# Juniordesignfilterandenvelopecircuitsche.net
KiCad netlist of a schematic drawn in EAGLE
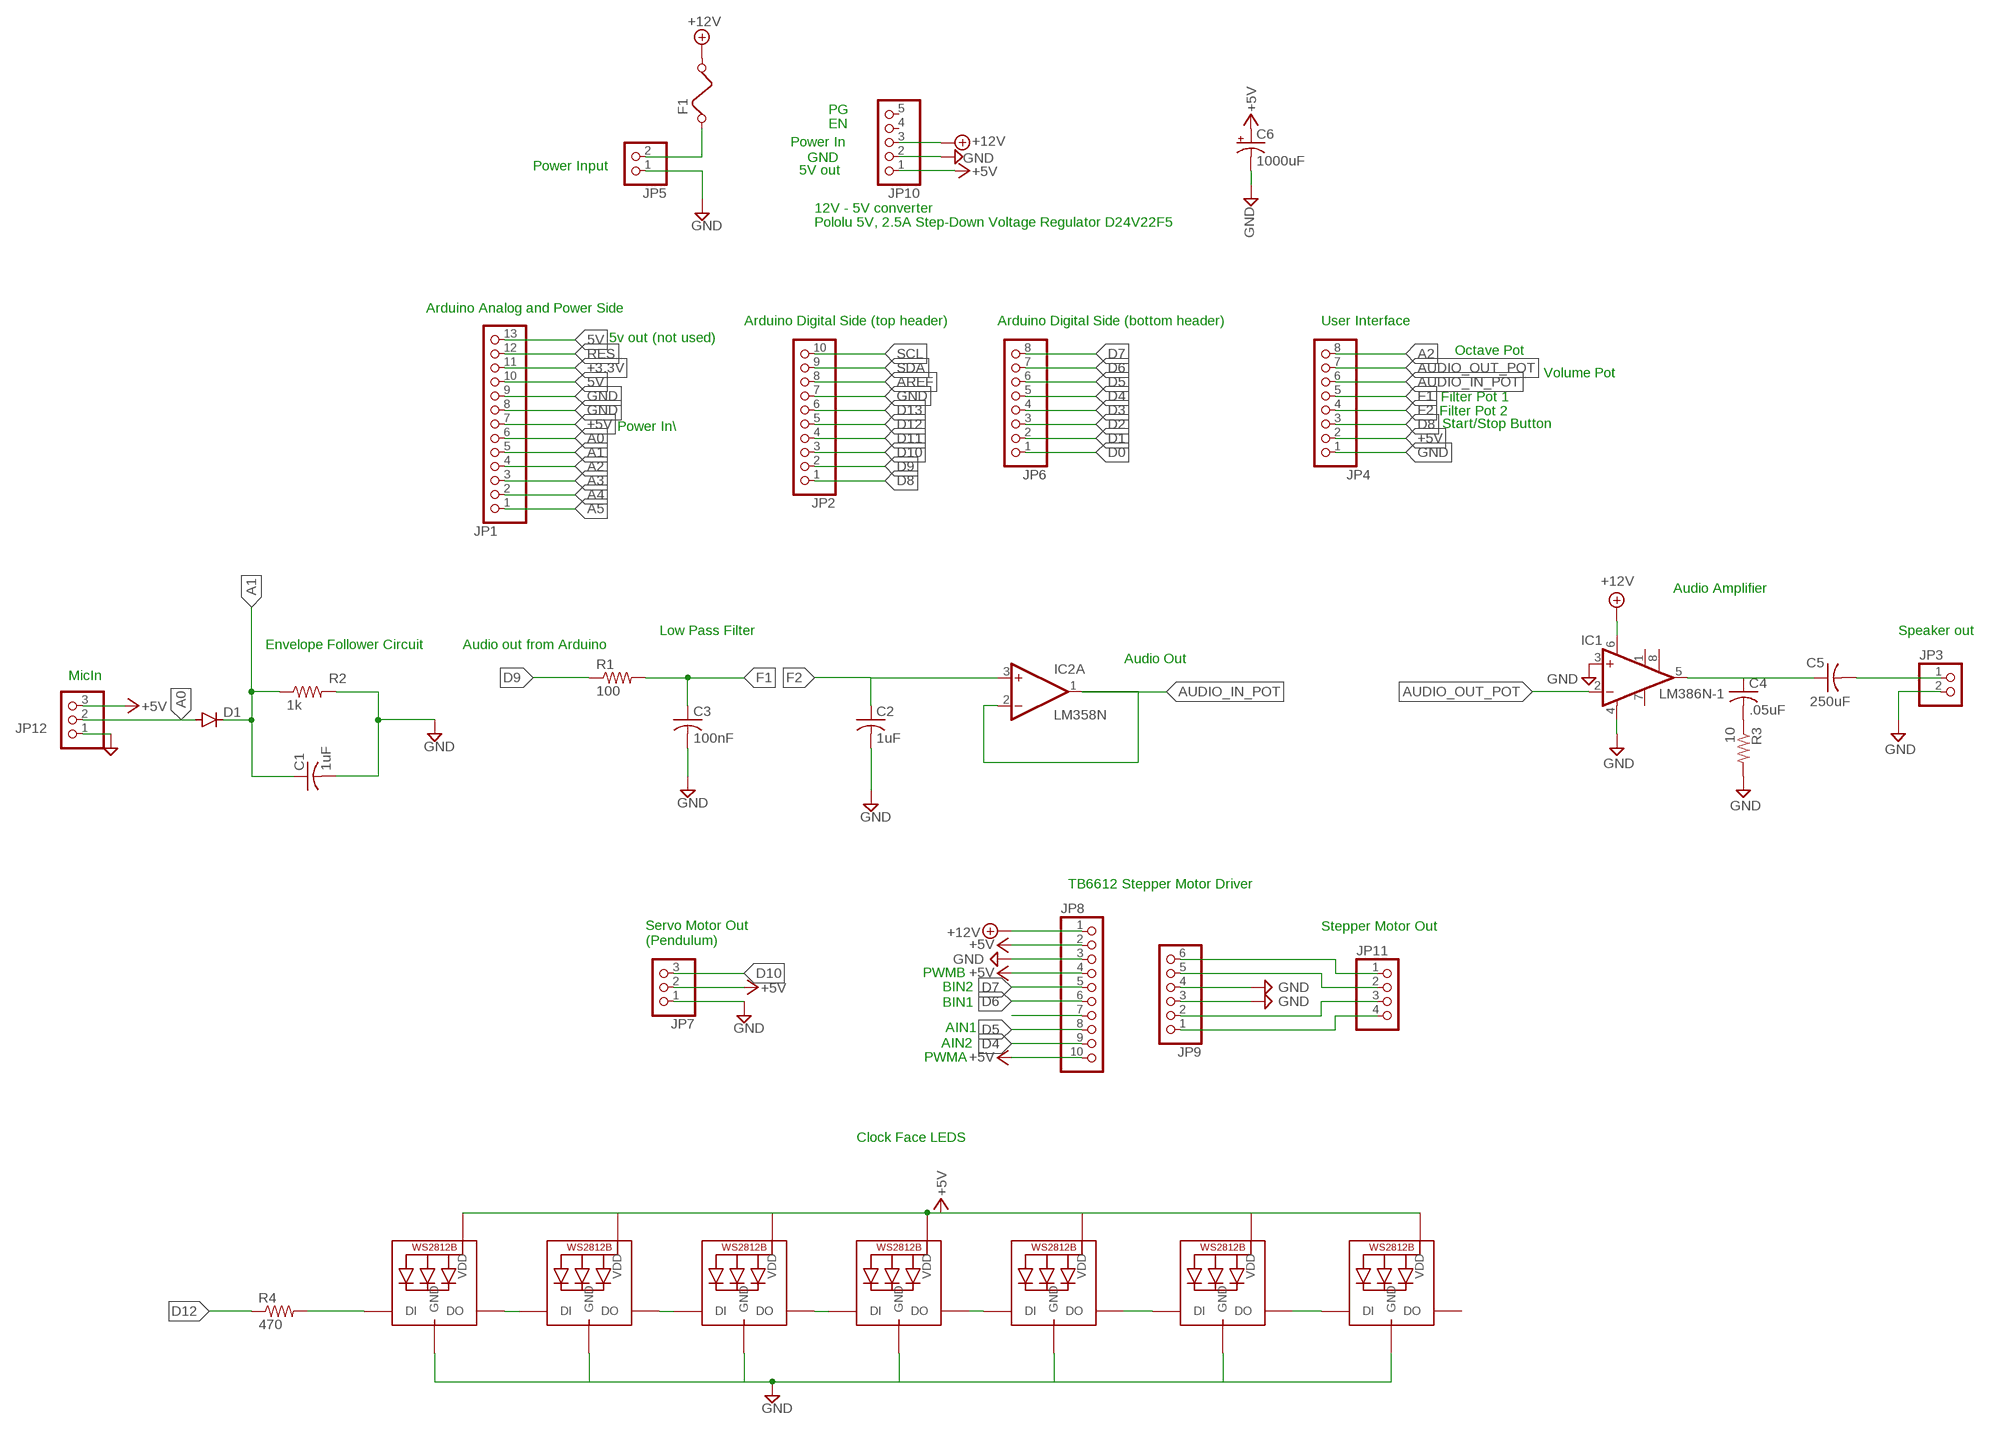
[diagram p0: schematic, sheet 1]

(export (version "E")
  (design (tool "Eeschema 10.0.6"))
  (components
    (comp (ref "C1")
      (value "1uF")
      (footprint "eagle-import:C025-050X050")
      (libsource (lib "eagle-import") (part "C-US025-050X050"))
    )
    (comp (ref "C2")
      (value "1uF")
      (footprint "eagle-import:C025-040X050")
      (libsource (lib "eagle-import") (part "C-US025-040X050"))
    )
    (comp (ref "C3")
      (value "100nF")
      (footprint "eagle-import:C025-040X050")
      (libsource (lib "eagle-import") (part "C-US025-040X050"))
    )
    (comp (ref "C4")
      (value ".05uF")
      (footprint "eagle-import:C025-040X050")
      (libsource (lib "eagle-import") (part "C-US025-040X050"))
    )
    (comp (ref "C5")
      (value "250uF")
      (footprint "eagle-import:C025-040X050")
      (libsource (lib "eagle-import") (part "C-US025-040X050"))
    )
    (comp (ref "C6")
      (value "1000uF")
      (footprint "eagle-import:E5-8,5")
      (libsource (lib "eagle-import") (part "CPOL-USE5-8.5"))
    )
    (comp (ref "D1")
      (value "1N4148DO35-7")
      (footprint "eagle-import:DO35-7")
      (libsource (lib "eagle-import") (part "1N4148DO35-7"))
    )
    (comp (ref "F1")
      (value "FUSE")
      (footprint "eagle-import:FUSE")
      (libsource (lib "eagle-import") (part "FUSE"))
    )
    (comp (ref "IC1")
      (value "LM386N-1")
      (footprint "eagle-import:DIL08")
      (libsource (lib "eagle-import") (part "LM386?-N1"))
    )
    (comp (ref "IC2")
      (value "LM358N")
      (footprint "eagle-import:DIL08")
      (libsource (lib "eagle-import") (part "LM358N"))
    )
    (comp (ref "JP1")
      (value "PINHD-1X13")
      (footprint "eagle-import:1X13")
      (libsource (lib "eagle-import") (part "PINHD-1X13"))
    )
    (comp (ref "JP2")
      (value "PINHD-1X10")
      (footprint "eagle-import:1X10")
      (libsource (lib "eagle-import") (part "PINHD-1X10"))
    )
    (comp (ref "JP3")
      (value "PINHD-1X2")
      (footprint "eagle-import:1X02")
      (libsource (lib "eagle-import") (part "PINHD-1X2"))
    )
    (comp (ref "JP4")
      (value "PINHD-1X8")
      (footprint "eagle-import:1X08")
      (libsource (lib "eagle-import") (part "PINHD-1X8"))
    )
    (comp (ref "JP5")
      (value "PINHD-1X2")
      (footprint "eagle-import:1X02")
      (libsource (lib "eagle-import") (part "PINHD-1X2"))
    )
    (comp (ref "JP6")
      (value "PINHD-1X8")
      (footprint "eagle-import:1X08")
      (libsource (lib "eagle-import") (part "PINHD-1X8"))
    )
    (comp (ref "JP7")
      (value "PINHD-1X3")
      (footprint "eagle-import:1X03")
      (libsource (lib "eagle-import") (part "PINHD-1X3"))
    )
    (comp (ref "JP8")
      (value "PINHD-1X10")
      (footprint "eagle-import:1X10")
      (libsource (lib "eagle-import") (part "PINHD-1X10"))
    )
    (comp (ref "JP9")
      (value "PINHD-1X6")
      (footprint "eagle-import:1X06")
      (libsource (lib "eagle-import") (part "PINHD-1X6"))
    )
    (comp (ref "JP10")
      (value "PINHD-1X5")
      (footprint "eagle-import:1X05")
      (libsource (lib "eagle-import") (part "PINHD-1X5"))
    )
    (comp (ref "JP11")
      (value "PINHD-1X4")
      (footprint "eagle-import:1X04")
      (libsource (lib "eagle-import") (part "PINHD-1X4"))
    )
    (comp (ref "JP12")
      (value "PINHD-1X3")
      (footprint "eagle-import:1X03")
      (libsource (lib "eagle-import") (part "PINHD-1X3"))
    )
    (comp (ref "LED2")
      (value "WS2812B_5050N")
      (footprint "eagle-import:WS2812B-NARROW")
      (libsource (lib "eagle-import") (part "WS2812B_5050N"))
    )
    (comp (ref "LED3")
      (value "WS2812B_5050N")
      (footprint "eagle-import:WS2812B-NARROW")
      (libsource (lib "eagle-import") (part "WS2812B_5050N"))
    )
    (comp (ref "LED4")
      (value "WS2812B_5050N")
      (footprint "eagle-import:WS2812B-NARROW")
      (libsource (lib "eagle-import") (part "WS2812B_5050N"))
    )
    (comp (ref "LED5")
      (value "WS2812B_5050N")
      (footprint "eagle-import:WS2812B-NARROW")
      (libsource (lib "eagle-import") (part "WS2812B_5050N"))
    )
    (comp (ref "LED6")
      (value "WS2812B_5050N")
      (footprint "eagle-import:WS2812B-NARROW")
      (libsource (lib "eagle-import") (part "WS2812B_5050N"))
    )
    (comp (ref "LED7")
      (value "WS2812B_5050N")
      (footprint "eagle-import:WS2812B-NARROW")
      (libsource (lib "eagle-import") (part "WS2812B_5050N"))
    )
    (comp (ref "LED8")
      (value "WS2812B_5050N")
      (footprint "eagle-import:WS2812B-NARROW")
      (libsource (lib "eagle-import") (part "WS2812B_5050N"))
    )
    (comp (ref "R1")
      (value "100")
      (footprint "eagle-import:0204_7")
      (libsource (lib "eagle-import") (part "R-US_0204/7"))
    )
    (comp (ref "R2")
      (value "1k")
      (footprint "eagle-import:0204_7")
      (libsource (lib "eagle-import") (part "R-US_0204/7"))
    )
    (comp (ref "R3")
      (value "10")
      (footprint "eagle-import:0204_7")
      (libsource (lib "eagle-import") (part "R-US_0204/7"))
    )
    (comp (ref "R4")
      (value "470")
      (footprint "eagle-import:0204_7")
      (libsource (lib "eagle-import") (part "R-US_0204/7"))
    )
  )
  (nets
    (net (code "1") (name "+3.3V") (class "Default")
      (node (ref "JP1") (pin "11") (pinfunction "11_11") (pintype "passive"))
    )
    (net (code "2") (name "+5V") (class "Default")
      (node (ref "C6") (pin "+") (pinfunction "+_+") (pintype "passive"))
      (node (ref "JP1") (pin "7") (pinfunction "7_7") (pintype "passive"))
      (node (ref "JP10") (pin "1") (pinfunction "1_1") (pintype "passive"))
      (node (ref "JP12") (pin "3") (pinfunction "3_3") (pintype "passive"))
      (node (ref "JP4") (pin "2") (pinfunction "2_2") (pintype "passive"))
      (node (ref "JP7") (pin "2") (pinfunction "2_2") (pintype "passive"))
      (node (ref "JP8") (pin "10") (pinfunction "10_10") (pintype "passive"))
      (node (ref "JP8") (pin "2") (pinfunction "2_2") (pintype "passive"))
      (node (ref "JP8") (pin "4") (pinfunction "4_4") (pintype "passive"))
      (node (ref "LED2") (pin "1-VDD") (pinfunction "VDD_1-VDD") (pintype "power_in"))
      (node (ref "LED3") (pin "1-VDD") (pinfunction "VDD_1-VDD") (pintype "power_in"))
      (node (ref "LED4") (pin "1-VDD") (pinfunction "VDD_1-VDD") (pintype "power_in"))
      (node (ref "LED5") (pin "1-VDD") (pinfunction "VDD_1-VDD") (pintype "power_in"))
      (node (ref "LED6") (pin "1-VDD") (pinfunction "VDD_1-VDD") (pintype "power_in"))
      (node (ref "LED7") (pin "1-VDD") (pinfunction "VDD_1-VDD") (pintype "power_in"))
      (node (ref "LED8") (pin "1-VDD") (pinfunction "VDD_1-VDD") (pintype "power_in"))
    )
    (net (code "3") (name "+12V") (class "Default")
      (node (ref "F1") (pin "2") (pinfunction "2_2") (pintype "passive"))
      (node (ref "IC1") (pin "6") (pinfunction "VS_6") (pintype "power_in"))
      (node (ref "JP10") (pin "3") (pinfunction "3_3") (pintype "passive"))
      (node (ref "JP8") (pin "1") (pinfunction "1_1") (pintype "passive"))
    )
    (net (code "4") (name "5V") (class "Default")
      (node (ref "JP1") (pin "10") (pinfunction "10_10") (pintype "passive"))
      (node (ref "JP1") (pin "13") (pinfunction "13_13") (pintype "passive"))
    )
    (net (code "5") (name "A0") (class "Default")
      (node (ref "D1") (pin "A") (pinfunction "A_A") (pintype "passive"))
      (node (ref "JP1") (pin "6") (pinfunction "6_6") (pintype "passive"))
      (node (ref "JP12") (pin "2") (pinfunction "2_2") (pintype "passive"))
    )
    (net (code "6") (name "A1") (class "Default")
      (node (ref "C1") (pin "1") (pinfunction "1_1") (pintype "passive"))
      (node (ref "D1") (pin "C") (pinfunction "C_C") (pintype "passive"))
      (node (ref "JP1") (pin "5") (pinfunction "5_5") (pintype "passive"))
      (node (ref "R2") (pin "1") (pinfunction "1_1") (pintype "passive"))
    )
    (net (code "7") (name "A2") (class "Default")
      (node (ref "JP1") (pin "4") (pinfunction "4_4") (pintype "passive"))
      (node (ref "JP4") (pin "8") (pinfunction "8_8") (pintype "passive"))
    )
    (net (code "8") (name "A3") (class "Default")
      (node (ref "JP1") (pin "3") (pinfunction "3_3") (pintype "passive"))
    )
    (net (code "9") (name "A4") (class "Default")
      (node (ref "JP1") (pin "2") (pinfunction "2_2") (pintype "passive"))
    )
    (net (code "10") (name "A5") (class "Default")
      (node (ref "JP1") (pin "1") (pinfunction "1_1") (pintype "passive"))
    )
    (net (code "11") (name "AREF") (class "Default")
      (node (ref "JP2") (pin "8") (pinfunction "8_8") (pintype "passive"))
    )
    (net (code "12") (name "AUDIO_IN_POT") (class "Default")
      (node (ref "IC2") (pin "1") (pinfunction "OUT_1") (pintype "output"))
      (node (ref "IC2") (pin "2") (pinfunction "-IN_2") (pintype "input"))
      (node (ref "JP4") (pin "6") (pinfunction "6_6") (pintype "passive"))
    )
    (net (code "13") (name "AUDIO_OUT_POT") (class "Default")
      (node (ref "IC1") (pin "2") (pinfunction "-IN_2") (pintype "input"))
      (node (ref "JP4") (pin "7") (pinfunction "7_7") (pintype "passive"))
    )
    (net (code "14") (name "D0") (class "Default")
      (node (ref "JP6") (pin "1") (pinfunction "1_1") (pintype "passive"))
    )
    (net (code "15") (name "D1") (class "Default")
      (node (ref "JP6") (pin "2") (pinfunction "2_2") (pintype "passive"))
    )
    (net (code "16") (name "D2") (class "Default")
      (node (ref "JP6") (pin "3") (pinfunction "3_3") (pintype "passive"))
    )
    (net (code "17") (name "D3") (class "Default")
      (node (ref "JP6") (pin "4") (pinfunction "4_4") (pintype "passive"))
    )
    (net (code "18") (name "D4") (class "Default")
      (node (ref "JP6") (pin "5") (pinfunction "5_5") (pintype "passive"))
      (node (ref "JP8") (pin "9") (pinfunction "9_9") (pintype "passive"))
    )
    (net (code "19") (name "D5") (class "Default")
      (node (ref "JP6") (pin "6") (pinfunction "6_6") (pintype "passive"))
      (node (ref "JP8") (pin "8") (pinfunction "8_8") (pintype "passive"))
    )
    (net (code "20") (name "D6") (class "Default")
      (node (ref "JP6") (pin "7") (pinfunction "7_7") (pintype "passive"))
      (node (ref "JP8") (pin "6") (pinfunction "6_6") (pintype "passive"))
    )
    (net (code "21") (name "D7") (class "Default")
      (node (ref "JP6") (pin "8") (pinfunction "8_8") (pintype "passive"))
      (node (ref "JP8") (pin "5") (pinfunction "5_5") (pintype "passive"))
    )
    (net (code "22") (name "D8") (class "Default")
      (node (ref "JP2") (pin "1") (pinfunction "1_1") (pintype "passive"))
      (node (ref "JP4") (pin "3") (pinfunction "3_3") (pintype "passive"))
    )
    (net (code "23") (name "D9") (class "Default")
      (node (ref "JP2") (pin "2") (pinfunction "2_2") (pintype "passive"))
      (node (ref "R1") (pin "1") (pinfunction "1_1") (pintype "passive"))
    )
    (net (code "24") (name "D10") (class "Default")
      (node (ref "JP2") (pin "3") (pinfunction "3_3") (pintype "passive"))
      (node (ref "JP7") (pin "3") (pinfunction "3_3") (pintype "passive"))
    )
    (net (code "25") (name "D11") (class "Default")
      (node (ref "JP2") (pin "4") (pinfunction "4_4") (pintype "passive"))
    )
    (net (code "26") (name "D12") (class "Default")
      (node (ref "JP2") (pin "5") (pinfunction "5_5") (pintype "passive"))
      (node (ref "R4") (pin "1") (pinfunction "1_1") (pintype "passive"))
    )
    (net (code "27") (name "D13") (class "Default")
      (node (ref "JP2") (pin "6") (pinfunction "6_6") (pintype "passive"))
    )
    (net (code "28") (name "F1") (class "Default")
      (node (ref "C3") (pin "1") (pinfunction "1_1") (pintype "passive"))
      (node (ref "JP4") (pin "5") (pinfunction "5_5") (pintype "passive"))
      (node (ref "R1") (pin "2") (pinfunction "2_2") (pintype "passive"))
    )
    (net (code "29") (name "F2") (class "Default")
      (node (ref "C2") (pin "1") (pinfunction "1_1") (pintype "passive"))
      (node (ref "IC2") (pin "3") (pinfunction "+IN_3") (pintype "input"))
      (node (ref "JP4") (pin "4") (pinfunction "4_4") (pintype "passive"))
    )
    (net (code "30") (name "GND") (class "Default")
      (node (ref "C1") (pin "2") (pinfunction "2_2") (pintype "passive"))
      (node (ref "C2") (pin "2") (pinfunction "2_2") (pintype "passive"))
      (node (ref "C3") (pin "2") (pinfunction "2_2") (pintype "passive"))
      (node (ref "C6") (pin "-") (pinfunction "-_-") (pintype "passive"))
      (node (ref "IC1") (pin "3") (pinfunction "+IN_3") (pintype "input"))
      (node (ref "IC1") (pin "4") (pinfunction "GND_4") (pintype "power_in"))
      (node (ref "JP1") (pin "8") (pinfunction "8_8") (pintype "passive"))
      (node (ref "JP1") (pin "9") (pinfunction "9_9") (pintype "passive"))
      (node (ref "JP10") (pin "2") (pinfunction "2_2") (pintype "passive"))
      (node (ref "JP12") (pin "1") (pinfunction "1_1") (pintype "passive"))
      (node (ref "JP2") (pin "7") (pinfunction "7_7") (pintype "passive"))
      (node (ref "JP3") (pin "2") (pinfunction "2_2") (pintype "passive"))
      (node (ref "JP4") (pin "1") (pinfunction "1_1") (pintype "passive"))
      (node (ref "JP5") (pin "1") (pinfunction "1_1") (pintype "passive"))
      (node (ref "JP7") (pin "1") (pinfunction "1_1") (pintype "passive"))
      (node (ref "JP8") (pin "3") (pinfunction "3_3") (pintype "passive"))
      (node (ref "JP9") (pin "3") (pinfunction "3_3") (pintype "passive"))
      (node (ref "JP9") (pin "4") (pinfunction "4_4") (pintype "passive"))
      (node (ref "LED2") (pin "3-GND") (pinfunction "GND_3-GND") (pintype "power_in"))
      (node (ref "LED3") (pin "3-GND") (pinfunction "GND_3-GND") (pintype "power_in"))
      (node (ref "LED4") (pin "3-GND") (pinfunction "GND_3-GND") (pintype "power_in"))
      (node (ref "LED5") (pin "3-GND") (pinfunction "GND_3-GND") (pintype "power_in"))
      (node (ref "LED6") (pin "3-GND") (pinfunction "GND_3-GND") (pintype "power_in"))
      (node (ref "LED7") (pin "3-GND") (pinfunction "GND_3-GND") (pintype "power_in"))
      (node (ref "LED8") (pin "3-GND") (pinfunction "GND_3-GND") (pintype "power_in"))
      (node (ref "R2") (pin "2") (pinfunction "2_2") (pintype "passive"))
      (node (ref "R3") (pin "2") (pinfunction "2_2") (pintype "passive"))
    )
    (net (code "31") (name "Net-(C4-Pad2)") (class "Default")
      (node (ref "C4") (pin "2") (pinfunction "2_2") (pintype "passive"))
      (node (ref "R3") (pin "1") (pinfunction "1_1") (pintype "passive"))
    )
    (net (code "32") (name "Net-(C5-Pad2)") (class "Default")
      (node (ref "C5") (pin "2") (pinfunction "2_2") (pintype "passive"))
      (node (ref "JP3") (pin "1") (pinfunction "1_1") (pintype "passive"))
    )
    (net (code "33") (name "Net-(F1-Pad1)") (class "Default")
      (node (ref "F1") (pin "1") (pinfunction "1_1") (pintype "passive"))
      (node (ref "JP5") (pin "2") (pinfunction "2_2") (pintype "passive"))
    )
    (net (code "34") (name "Net-(IC1-OUT)") (class "Default")
      (node (ref "C4") (pin "1") (pinfunction "1_1") (pintype "passive"))
      (node (ref "C5") (pin "1") (pinfunction "1_1") (pintype "passive"))
      (node (ref "IC1") (pin "5") (pinfunction "OUT_5") (pintype "output"))
    )
    (net (code "35") (name "Net-(JP11-Pad1)") (class "Default")
      (node (ref "JP11") (pin "1") (pinfunction "1_1") (pintype "passive"))
      (node (ref "JP9") (pin "6") (pinfunction "6_6") (pintype "passive"))
    )
    (net (code "36") (name "Net-(JP11-Pad2)") (class "Default")
      (node (ref "JP11") (pin "2") (pinfunction "2_2") (pintype "passive"))
      (node (ref "JP9") (pin "5") (pinfunction "5_5") (pintype "passive"))
    )
    (net (code "37") (name "Net-(JP11-Pad3)") (class "Default")
      (node (ref "JP11") (pin "3") (pinfunction "3_3") (pintype "passive"))
      (node (ref "JP9") (pin "2") (pinfunction "2_2") (pintype "passive"))
    )
    (net (code "38") (name "Net-(JP11-Pad4)") (class "Default")
      (node (ref "JP11") (pin "4") (pinfunction "4_4") (pintype "passive"))
      (node (ref "JP9") (pin "1") (pinfunction "1_1") (pintype "passive"))
    )
    (net (code "39") (name "Net-(LED2-DI)") (class "Default")
      (node (ref "LED2") (pin "4-DIN") (pinfunction "DI_4-DIN") (pintype "input"))
      (node (ref "R4") (pin "2") (pinfunction "2_2") (pintype "passive"))
    )
    (net (code "40") (name "Net-(LED2-DO)") (class "Default")
      (node (ref "LED2") (pin "2-DOUT") (pinfunction "DO_2-DOUT") (pintype "output"))
      (node (ref "LED3") (pin "4-DIN") (pinfunction "DI_4-DIN") (pintype "input"))
    )
    (net (code "41") (name "Net-(LED3-DO)") (class "Default")
      (node (ref "LED3") (pin "2-DOUT") (pinfunction "DO_2-DOUT") (pintype "output"))
      (node (ref "LED4") (pin "4-DIN") (pinfunction "DI_4-DIN") (pintype "input"))
    )
    (net (code "42") (name "Net-(LED4-DO)") (class "Default")
      (node (ref "LED4") (pin "2-DOUT") (pinfunction "DO_2-DOUT") (pintype "output"))
      (node (ref "LED5") (pin "4-DIN") (pinfunction "DI_4-DIN") (pintype "input"))
    )
    (net (code "43") (name "Net-(LED5-DO)") (class "Default")
      (node (ref "LED5") (pin "2-DOUT") (pinfunction "DO_2-DOUT") (pintype "output"))
      (node (ref "LED6") (pin "4-DIN") (pinfunction "DI_4-DIN") (pintype "input"))
    )
    (net (code "44") (name "Net-(LED6-DO)") (class "Default")
      (node (ref "LED6") (pin "2-DOUT") (pinfunction "DO_2-DOUT") (pintype "output"))
      (node (ref "LED7") (pin "4-DIN") (pinfunction "DI_4-DIN") (pintype "input"))
    )
    (net (code "45") (name "Net-(LED7-DO)") (class "Default")
      (node (ref "LED7") (pin "2-DOUT") (pinfunction "DO_2-DOUT") (pintype "output"))
      (node (ref "LED8") (pin "4-DIN") (pinfunction "DI_4-DIN") (pintype "input"))
    )
    (net (code "46") (name "RES") (class "Default")
      (node (ref "JP1") (pin "12") (pinfunction "12_12") (pintype "passive"))
    )
    (net (code "47") (name "SCL") (class "Default")
      (node (ref "JP2") (pin "10") (pinfunction "10_10") (pintype "passive"))
    )
    (net (code "48") (name "SDA") (class "Default")
      (node (ref "JP2") (pin "9") (pinfunction "9_9") (pintype "passive"))
    )
    (net (code "49") (name "unconnected-(IC1-BYPASS-Pad7)") (class "Default")
      (node (ref "IC1") (pin "7") (pinfunction "BYPASS_7") (pintype "passive"))
    )
    (net (code "50") (name "unconnected-(IC1-GAIN-Pad1)") (class "Default")
      (node (ref "IC1") (pin "1") (pinfunction "GAIN_1") (pintype "passive"))
    )
    (net (code "51") (name "unconnected-(IC1-GAIN-Pad8)") (class "Default")
      (node (ref "IC1") (pin "8") (pinfunction "GAIN_8") (pintype "passive"))
    )
    (net (code "52") (name "unconnected-(JP8-Pad7)") (class "Default")
      (node (ref "JP8") (pin "7") (pinfunction "7_7") (pintype "passive"))
    )
    (net (code "53") (name "unconnected-(JP10-Pad4)") (class "Default")
      (node (ref "JP10") (pin "4") (pinfunction "4_4") (pintype "passive"))
    )
    (net (code "54") (name "unconnected-(JP10-Pad5)") (class "Default")
      (node (ref "JP10") (pin "5") (pinfunction "5_5") (pintype "passive"))
    )
    (net (code "55") (name "unconnected-(LED8-DO-Pad2-DOUT)") (class "Default")
      (node (ref "LED8") (pin "2-DOUT") (pinfunction "DO_2-DOUT") (pintype "output"))
    )
  )
)
